# SCH_usb-hub_2025-07-20.net
KiCad netlist of a schematic drawn in EasyEDA
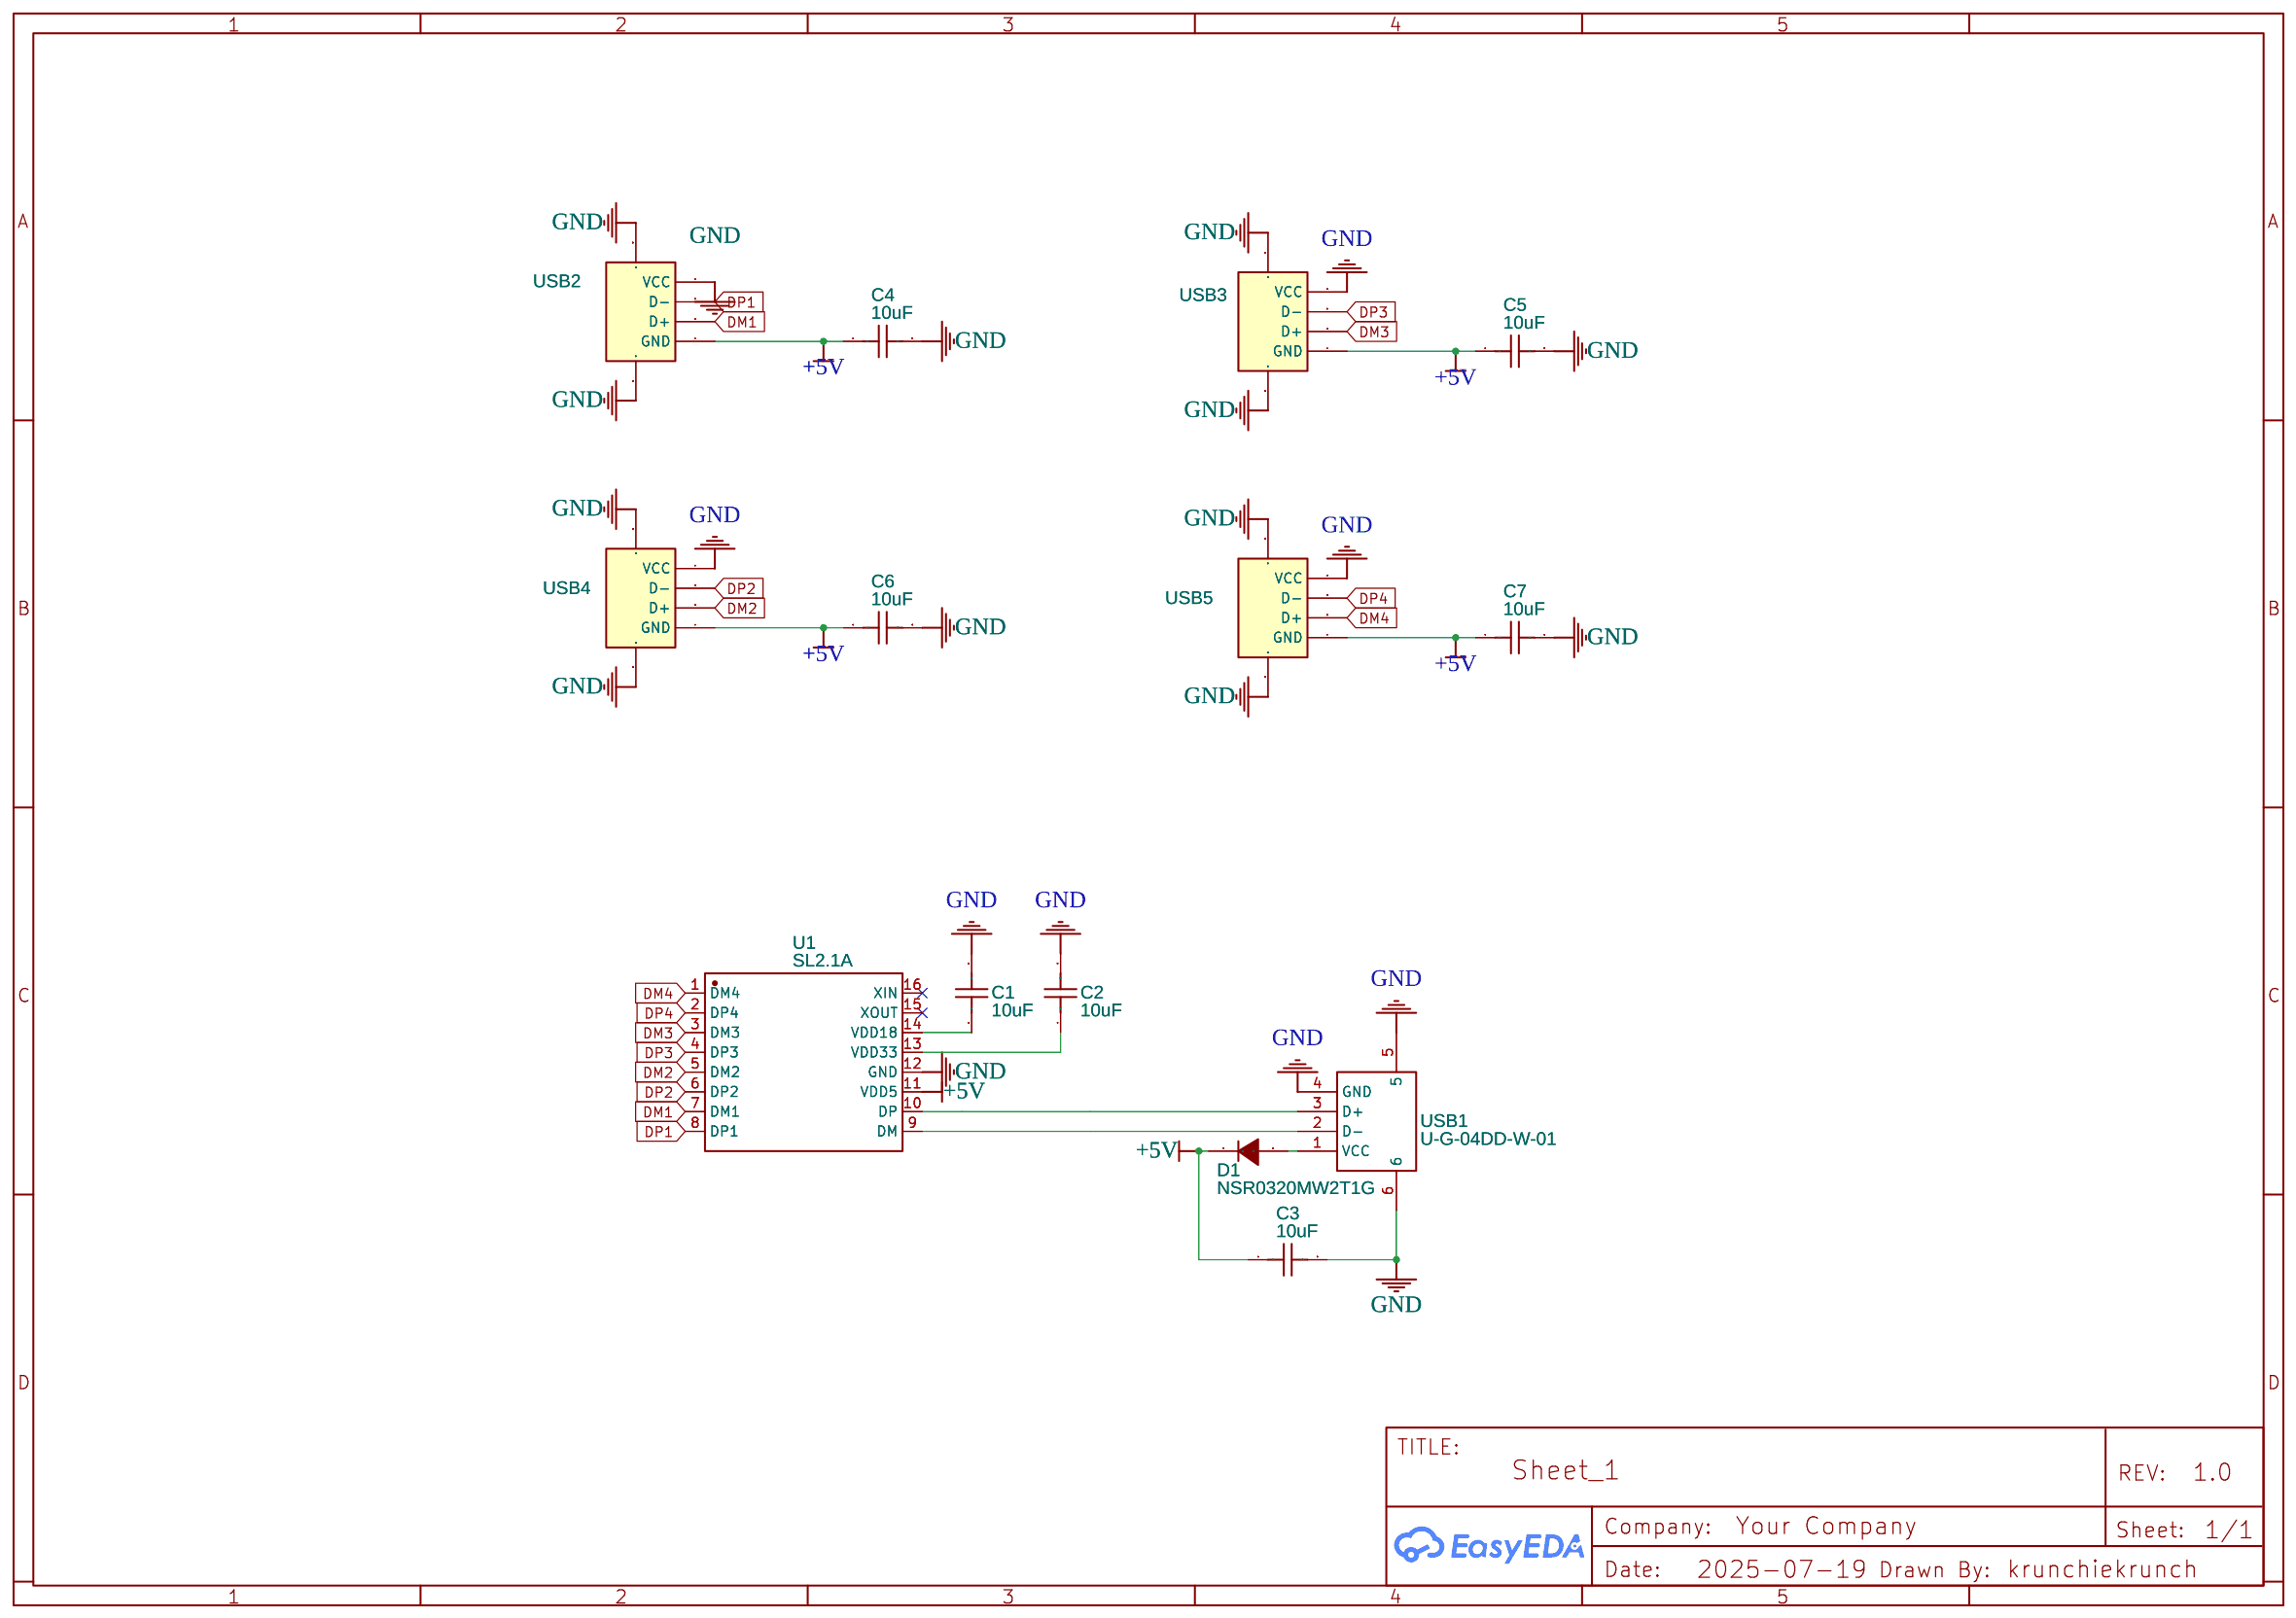
[diagram p0: schematic sheet]

(export (version "E")
  (design (tool "Eeschema 10.0.6"))
  (components
    (comp (ref "C1")
      (value "10uF")
      (fields
        (field (name "Manufacturer Part") "CL21A106KAYNNNE")
        (field (name "Manufacturer") "SAMSUNG(三星)")
      )
      (libsource (lib "") (part "CL21A106KAYNNNE_1"))
    )
    (comp (ref "C2")
      (value "10uF")
      (fields
        (field (name "Manufacturer Part") "CL21A106KAYNNNE")
        (field (name "Manufacturer") "SAMSUNG(三星)")
      )
      (libsource (lib "") (part "CL21A106KAYNNNE_1"))
    )
    (comp (ref "C3")
      (value "10uF")
      (fields
        (field (name "Manufacturer Part") "CL21A106KAYNNNE")
        (field (name "Manufacturer") "SAMSUNG(三星)")
      )
      (libsource (lib "") (part "CL21A106KAYNNNE"))
    )
    (comp (ref "C4")
      (value "10uF")
      (fields
        (field (name "Manufacturer Part") "CL21A106KAYNNNE")
        (field (name "Manufacturer") "SAMSUNG(三星)")
      )
      (libsource (lib "") (part "CL21A106KAYNNNE"))
    )
    (comp (ref "C5")
      (value "10uF")
      (fields
        (field (name "Manufacturer Part") "CL21A106KAYNNNE")
        (field (name "Manufacturer") "SAMSUNG(三星)")
      )
      (libsource (lib "") (part "CL21A106KAYNNNE"))
    )
    (comp (ref "C6")
      (value "10uF")
      (fields
        (field (name "Manufacturer Part") "CL21A106KAYNNNE")
        (field (name "Manufacturer") "SAMSUNG(三星)")
      )
      (libsource (lib "") (part "CL21A106KAYNNNE"))
    )
    (comp (ref "C7")
      (value "10uF")
      (fields
        (field (name "Manufacturer Part") "CL21A106KAYNNNE")
        (field (name "Manufacturer") "SAMSUNG(三星)")
      )
      (libsource (lib "") (part "CL21A106KAYNNNE"))
    )
    (comp (ref "D1")
      (value "NSR0320MW2T1G")
      (fields (field (name "Manufacturer") "onsemi(安森美)"))
      (libsource (lib "") (part "NSR0320MW2T1G"))
    )
    (comp (ref "U1")
      (value "SL2.1A")
      (fields (field (name "Manufacturer") "CoreChips(和芯润德)"))
      (libsource (lib "") (part "SL2.1A"))
    )
    (comp (ref "USB1")
      (value "U-G-04DD-W-01")
      (fields (field (name "Manufacturer Part") "U-G-O4DD-W-1") (field (name "Manufacturer") "韩国韩荣"))
      (libsource (lib "") (part "U-G-04DD-W-01"))
    )
    (comp (ref "USB2")
      (value "USB A/F 90° Outside the buckle straight foot")
      (fields (field (name "Manufacturer Part") "901-211A1021D10100") (field (name "Manufacturer") "精拓金"))
      (libsource (lib "") (part "USB A/F 90° Outside the buckle straight foot"))
    )
    (comp (ref "USB3")
      (value "USB A/F 90° Outside the buckle straight foot")
      (fields (field (name "Manufacturer Part") "901-211A1021D10100") (field (name "Manufacturer") "精拓金"))
      (libsource (lib "") (part "USB A/F 90° Outside the buckle straight foot"))
    )
    (comp (ref "USB4")
      (value "USB A/F 90° Outside the buckle straight foot")
      (fields (field (name "Manufacturer Part") "901-211A1021D10100") (field (name "Manufacturer") "精拓金"))
      (libsource (lib "") (part "USB A/F 90° Outside the buckle straight foot"))
    )
    (comp (ref "USB5")
      (value "USB A/F 90° Outside the buckle straight foot")
      (fields (field (name "Manufacturer Part") "901-211A1021D10100") (field (name "Manufacturer") "精拓金"))
      (libsource (lib "") (part "USB A/F 90° Outside the buckle straight foot"))
    )
  )
  (nets
    (net (code "1") (name "+5V") (class "Default")
      (node (ref "C3") (pin "1") (pinfunction "1_1") (pintype "unspecified"))
      (node (ref "C4") (pin "1") (pinfunction "1_1") (pintype "unspecified"))
      (node (ref "C5") (pin "1") (pinfunction "1_1") (pintype "unspecified"))
      (node (ref "C6") (pin "1") (pinfunction "1_1") (pintype "unspecified"))
      (node (ref "C7") (pin "1") (pinfunction "1_1") (pintype "unspecified"))
      (node (ref "D1") (pin "1") (pinfunction "C_1") (pintype "unspecified"))
      (node (ref "U1") (pin "11") (pinfunction "VDD5_11") (pintype "unspecified"))
      (node (ref "USB2") (pin "4") (pinfunction "GND_4") (pintype "input"))
      (node (ref "USB3") (pin "4") (pinfunction "GND_4") (pintype "input"))
      (node (ref "USB4") (pin "4") (pinfunction "GND_4") (pintype "input"))
      (node (ref "USB5") (pin "4") (pinfunction "GND_4") (pintype "input"))
    )
    (net (code "2") (name "DM1") (class "Default")
      (node (ref "U1") (pin "7") (pinfunction "DM1_7") (pintype "unspecified"))
      (node (ref "USB2") (pin "3") (pinfunction "D+_3") (pintype "input"))
    )
    (net (code "3") (name "DM2") (class "Default")
      (node (ref "U1") (pin "5") (pinfunction "DM2_5") (pintype "unspecified"))
      (node (ref "USB4") (pin "3") (pinfunction "D+_3") (pintype "input"))
    )
    (net (code "4") (name "DM3") (class "Default")
      (node (ref "U1") (pin "3") (pinfunction "DM3_3") (pintype "unspecified"))
      (node (ref "USB3") (pin "3") (pinfunction "D+_3") (pintype "input"))
    )
    (net (code "5") (name "DM4") (class "Default")
      (node (ref "U1") (pin "1") (pinfunction "DM4_1") (pintype "unspecified"))
      (node (ref "USB5") (pin "3") (pinfunction "D+_3") (pintype "input"))
    )
    (net (code "6") (name "DP1") (class "Default")
      (node (ref "U1") (pin "8") (pinfunction "DP1_8") (pintype "unspecified"))
      (node (ref "USB2") (pin "2") (pinfunction "D-_2") (pintype "input"))
    )
    (net (code "7") (name "DP2") (class "Default")
      (node (ref "U1") (pin "6") (pinfunction "DP2_6") (pintype "unspecified"))
      (node (ref "USB4") (pin "2") (pinfunction "D-_2") (pintype "input"))
    )
    (net (code "8") (name "DP3") (class "Default")
      (node (ref "U1") (pin "4") (pinfunction "DP3_4") (pintype "unspecified"))
      (node (ref "USB3") (pin "2") (pinfunction "D-_2") (pintype "input"))
    )
    (net (code "9") (name "DP4") (class "Default")
      (node (ref "U1") (pin "2") (pinfunction "DP4_2") (pintype "unspecified"))
      (node (ref "USB5") (pin "2") (pinfunction "D-_2") (pintype "input"))
    )
    (net (code "10") (name "GND") (class "Default")
      (node (ref "C1") (pin "2") (pinfunction "2_2") (pintype "unspecified"))
      (node (ref "C2") (pin "2") (pinfunction "2_2") (pintype "unspecified"))
      (node (ref "C3") (pin "2") (pinfunction "2_2") (pintype "unspecified"))
      (node (ref "C4") (pin "2") (pinfunction "2_2") (pintype "unspecified"))
      (node (ref "C5") (pin "2") (pinfunction "2_2") (pintype "unspecified"))
      (node (ref "C6") (pin "2") (pinfunction "2_2") (pintype "unspecified"))
      (node (ref "C7") (pin "2") (pinfunction "2_2") (pintype "unspecified"))
      (node (ref "U1") (pin "12") (pinfunction "GND_12") (pintype "unspecified"))
      (node (ref "USB1") (pin "4") (pinfunction "GND_4") (pintype "unspecified"))
      (node (ref "USB1") (pin "5") (pinfunction "5_5") (pintype "unspecified"))
      (node (ref "USB1") (pin "6") (pinfunction "6_6") (pintype "unspecified"))
      (node (ref "USB2") (pin "0") (pinfunction "0_0") (pintype "unspecified"))
      (node (ref "USB2") (pin "1") (pinfunction "VCC_1") (pintype "input"))
      (node (ref "USB3") (pin "0") (pinfunction "0_0") (pintype "unspecified"))
      (node (ref "USB3") (pin "1") (pinfunction "VCC_1") (pintype "input"))
      (node (ref "USB4") (pin "0") (pinfunction "0_0") (pintype "unspecified"))
      (node (ref "USB4") (pin "1") (pinfunction "VCC_1") (pintype "input"))
      (node (ref "USB5") (pin "0") (pinfunction "0_0") (pintype "unspecified"))
      (node (ref "USB5") (pin "1") (pinfunction "VCC_1") (pintype "input"))
    )
    (net (code "11") (name "Net-(D1-A)") (class "Default")
      (node (ref "D1") (pin "2") (pinfunction "A_2") (pintype "unspecified"))
      (node (ref "USB1") (pin "1") (pinfunction "VCC_1") (pintype "unspecified"))
    )
    (net (code "12") (name "Net-(U1-DM)") (class "Default")
      (node (ref "U1") (pin "9") (pinfunction "DM_9") (pintype "unspecified"))
      (node (ref "USB1") (pin "2") (pinfunction "D-_2") (pintype "unspecified"))
    )
    (net (code "13") (name "Net-(U1-DP)") (class "Default")
      (node (ref "U1") (pin "10") (pinfunction "DP_10") (pintype "unspecified"))
      (node (ref "USB1") (pin "3") (pinfunction "D+_3") (pintype "unspecified"))
    )
    (net (code "14") (name "Net-(U1-VDD18)") (class "Default")
      (node (ref "C1") (pin "1") (pinfunction "1_1") (pintype "unspecified"))
      (node (ref "U1") (pin "14") (pinfunction "VDD18_14") (pintype "unspecified"))
    )
    (net (code "15") (name "Net-(U1-VDD33)") (class "Default")
      (node (ref "C2") (pin "1") (pinfunction "1_1") (pintype "unspecified"))
      (node (ref "U1") (pin "13") (pinfunction "VDD33_13") (pintype "unspecified"))
    )
    (net (code "16") (name "unconnected-(U1-XIN-Pad16)") (class "Default")
      (node (ref "U1") (pin "16") (pinfunction "XIN_16") (pintype "unspecified+no_connect"))
    )
    (net (code "17") (name "unconnected-(U1-XOUT-Pad15)") (class "Default")
      (node (ref "U1") (pin "15") (pinfunction "XOUT_15") (pintype "unspecified+no_connect"))
    )
  )
)
